# 1_3_OLED_FOR_1U.net
KiCad netlist of a schematic drawn in EAGLE
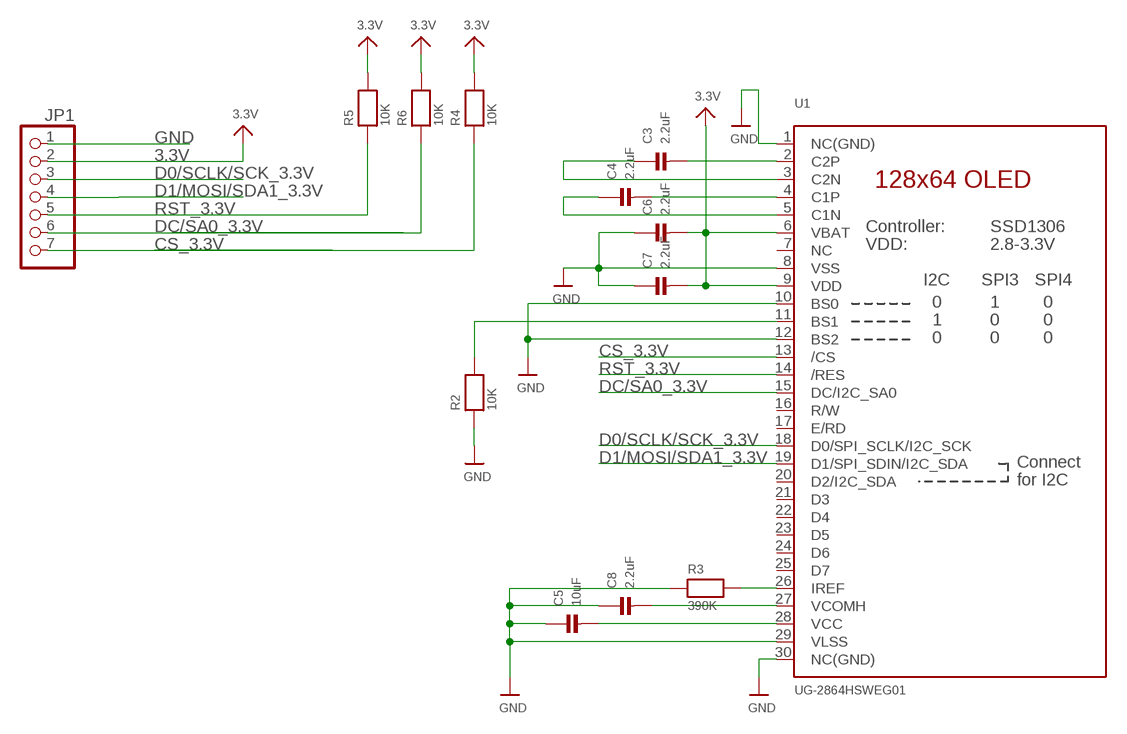
[diagram p0: schematic, sheet 1]

(export (version "E")
  (design (tool "Eeschema 10.0.6"))
  (components
    (comp (ref "C3")
      (value "2.2uF")
      (footprint "eagle-import:0603-MINI")
      (libsource (lib "eagle-import") (part "CAP_CERAMIC0603MINI"))
    )
    (comp (ref "C4")
      (value "2.2uF")
      (footprint "eagle-import:0603-MINI")
      (libsource (lib "eagle-import") (part "CAP_CERAMIC0603MINI"))
    )
    (comp (ref "C5")
      (value "10uF")
      (footprint "eagle-import:0603-MINI")
      (libsource (lib "eagle-import") (part "CAP_CERAMIC0603MINI"))
    )
    (comp (ref "C6")
      (value "2.2uF")
      (footprint "eagle-import:0603-MINI")
      (libsource (lib "eagle-import") (part "CAP_CERAMIC0603MINI"))
    )
    (comp (ref "C7")
      (value "2.2uF")
      (footprint "eagle-import:0603-MINI")
      (libsource (lib "eagle-import") (part "CAP_CERAMIC0603MINI"))
    )
    (comp (ref "C8")
      (value "2.2uF")
      (footprint "eagle-import:0603-MINI")
      (libsource (lib "eagle-import") (part "CAP_CERAMIC0603MINI"))
    )
    (comp (ref "JP1")
      (value "HEADER-1X7ROUND")
      (footprint "eagle-import:1X07_ROUND")
      (fields (field (name "SPICEPREFIX") "X"))
      (libsource (lib "eagle-import") (part "HEADER-1X7ROUND"))
    )
    (comp (ref "R2")
      (value "10K")
      (footprint "eagle-import:0603-MINI")
      (libsource (lib "eagle-import") (part "RESISTOR0603MINI"))
    )
    (comp (ref "R3")
      (value "390K")
      (footprint "eagle-import:0603-MINI")
      (libsource (lib "eagle-import") (part "RESISTOR0603MINI"))
    )
    (comp (ref "R4")
      (value "10K")
      (footprint "eagle-import:0603-MINI")
      (libsource (lib "eagle-import") (part "RESISTOR0603MINI"))
    )
    (comp (ref "R5")
      (value "10K")
      (footprint "eagle-import:0603-MINI")
      (libsource (lib "eagle-import") (part "RESISTOR0603MINI"))
    )
    (comp (ref "R6")
      (value "10K")
      (footprint "eagle-import:0603-MINI")
      (libsource (lib "eagle-import") (part "RESISTOR0603MINI"))
    )
    (comp (ref "U1")
      (value "UG-2864HSWEG01")
      (footprint "eagle-import:UG-2864HSWEG01_1.3_WRAPAROUND")
      (libsource (lib "eagle-import") (part "DISP_OLED_UG-2864HSWEG01"))
    )
  )
  (nets
    (net (code "1") (name "/CS_3.3V") (class "Default")
      (node (ref "JP1") (pin "7") (pinfunction "7_7") (pintype "passive"))
      (node (ref "R4") (pin "1") (pinfunction "1_1") (pintype "passive"))
      (node (ref "U1") (pin "13") (pinfunction "/CS_13") (pintype "input"))
    )
    (net (code "2") (name "/D0{slash}SCLK{slash}SCK_3.3V") (class "Default")
      (node (ref "JP1") (pin "3") (pinfunction "3_3") (pintype "passive"))
      (node (ref "U1") (pin "18") (pinfunction "D0/SPI_SCLK/I2C_SCK_18") (pintype "bidirectional"))
    )
    (net (code "3") (name "/D1{slash}MOSI{slash}SDA1_3.3V") (class "Default")
      (node (ref "JP1") (pin "4") (pinfunction "4_4") (pintype "passive"))
      (node (ref "U1") (pin "19") (pinfunction "D1/SPI_SDIN/I2C_SDA_19") (pintype "bidirectional"))
    )
    (net (code "4") (name "/DC{slash}SA0_3.3V") (class "Default")
      (node (ref "JP1") (pin "6") (pinfunction "6_6") (pintype "passive"))
      (node (ref "R6") (pin "1") (pinfunction "1_1") (pintype "passive"))
      (node (ref "U1") (pin "15") (pinfunction "DC/I2C_SA0_15") (pintype "input"))
    )
    (net (code "5") (name "/RST_3.3V") (class "Default")
      (node (ref "JP1") (pin "5") (pinfunction "5_5") (pintype "passive"))
      (node (ref "R5") (pin "1") (pinfunction "1_1") (pintype "passive"))
      (node (ref "U1") (pin "14") (pinfunction "/RES_14") (pintype "input"))
    )
    (net (code "6") (name "3.3V") (class "Default")
      (node (ref "C6") (pin "2") (pinfunction "P$2_2") (pintype "passive"))
      (node (ref "C7") (pin "2") (pinfunction "P$2_2") (pintype "passive"))
      (node (ref "JP1") (pin "2") (pinfunction "2_2") (pintype "passive"))
      (node (ref "R4") (pin "2") (pinfunction "2_2") (pintype "passive"))
      (node (ref "R5") (pin "2") (pinfunction "2_2") (pintype "passive"))
      (node (ref "R6") (pin "2") (pinfunction "2_2") (pintype "passive"))
      (node (ref "U1") (pin "6") (pinfunction "VBAT_6") (pintype "input"))
      (node (ref "U1") (pin "9") (pinfunction "VDD_9") (pintype "power_in"))
    )
    (net (code "7") (name "GND") (class "Default")
      (node (ref "C5") (pin "1") (pinfunction "P$1_1") (pintype "passive"))
      (node (ref "C6") (pin "1") (pinfunction "P$1_1") (pintype "passive"))
      (node (ref "C7") (pin "1") (pinfunction "P$1_1") (pintype "passive"))
      (node (ref "C8") (pin "1") (pinfunction "P$1_1") (pintype "passive"))
      (node (ref "JP1") (pin "1") (pinfunction "1_1") (pintype "passive"))
      (node (ref "R2") (pin "1") (pinfunction "1_1") (pintype "passive"))
      (node (ref "R3") (pin "1") (pinfunction "1_1") (pintype "passive"))
      (node (ref "U1") (pin "1") (pinfunction "NC(GND)_1") (pintype "input"))
      (node (ref "U1") (pin "10") (pinfunction "BS0_10") (pintype "input"))
      (node (ref "U1") (pin "12") (pinfunction "BS2_12") (pintype "input"))
      (node (ref "U1") (pin "29") (pinfunction "VLSS_29") (pintype "power_in"))
      (node (ref "U1") (pin "30") (pinfunction "NC(GND)_30") (pintype "input"))
      (node (ref "U1") (pin "8") (pinfunction "VSS_8") (pintype "power_in"))
    )
    (net (code "8") (name "Net-(C3-P$1)") (class "Default")
      (node (ref "C3") (pin "1") (pinfunction "P$1_1") (pintype "passive"))
      (node (ref "U1") (pin "3") (pinfunction "C2N_3") (pintype "input"))
    )
    (net (code "9") (name "Net-(C3-P$2)") (class "Default")
      (node (ref "C3") (pin "2") (pinfunction "P$2_2") (pintype "passive"))
      (node (ref "U1") (pin "2") (pinfunction "C2P_2") (pintype "input"))
    )
    (net (code "10") (name "Net-(C4-P$1)") (class "Default")
      (node (ref "C4") (pin "1") (pinfunction "P$1_1") (pintype "passive"))
      (node (ref "U1") (pin "5") (pinfunction "C1N_5") (pintype "input"))
    )
    (net (code "11") (name "Net-(C4-P$2)") (class "Default")
      (node (ref "C4") (pin "2") (pinfunction "P$2_2") (pintype "passive"))
      (node (ref "U1") (pin "4") (pinfunction "C1P_4") (pintype "input"))
    )
    (net (code "12") (name "Net-(C5-P$2)") (class "Default")
      (node (ref "C5") (pin "2") (pinfunction "P$2_2") (pintype "passive"))
      (node (ref "U1") (pin "28") (pinfunction "VCC_28") (pintype "power_in"))
    )
    (net (code "13") (name "Net-(C8-P$2)") (class "Default")
      (node (ref "C8") (pin "2") (pinfunction "P$2_2") (pintype "passive"))
      (node (ref "U1") (pin "27") (pinfunction "VCOMH_27") (pintype "output"))
    )
    (net (code "14") (name "Net-(U1-BS1)") (class "Default")
      (node (ref "R2") (pin "2") (pinfunction "2_2") (pintype "passive"))
      (node (ref "U1") (pin "11") (pinfunction "BS1_11") (pintype "input"))
    )
    (net (code "15") (name "Net-(U1-IREF)") (class "Default")
      (node (ref "R3") (pin "2") (pinfunction "2_2") (pintype "passive"))
      (node (ref "U1") (pin "26") (pinfunction "IREF_26") (pintype "input"))
    )
    (net (code "16") (name "unconnected-(U1-D2{slash}I2C_SDA-Pad20)") (class "Default")
      (node (ref "U1") (pin "20") (pinfunction "D2/I2C_SDA_20") (pintype "bidirectional"))
    )
    (net (code "17") (name "unconnected-(U1-D3-Pad21)") (class "Default")
      (node (ref "U1") (pin "21") (pinfunction "D3_21") (pintype "bidirectional"))
    )
    (net (code "18") (name "unconnected-(U1-D4-Pad22)") (class "Default")
      (node (ref "U1") (pin "22") (pinfunction "D4_22") (pintype "bidirectional"))
    )
    (net (code "19") (name "unconnected-(U1-D5-Pad23)") (class "Default")
      (node (ref "U1") (pin "23") (pinfunction "D5_23") (pintype "bidirectional"))
    )
    (net (code "20") (name "unconnected-(U1-D6-Pad24)") (class "Default")
      (node (ref "U1") (pin "24") (pinfunction "D6_24") (pintype "bidirectional"))
    )
    (net (code "21") (name "unconnected-(U1-D7-Pad25)") (class "Default")
      (node (ref "U1") (pin "25") (pinfunction "D7_25") (pintype "bidirectional"))
    )
    (net (code "22") (name "unconnected-(U1-E{slash}RD-Pad17)") (class "Default")
      (node (ref "U1") (pin "17") (pinfunction "E/RD_17") (pintype "input"))
    )
    (net (code "23") (name "unconnected-(U1-NC-Pad7)") (class "Default")
      (node (ref "U1") (pin "7") (pinfunction "NC_7") (pintype "no_connect"))
    )
    (net (code "24") (name "unconnected-(U1-R{slash}W-Pad16)") (class "Default")
      (node (ref "U1") (pin "16") (pinfunction "R/W_16") (pintype "input"))
    )
  )
)
